# ADC.net
KiCad netlist of a schematic drawn in Altium Designer
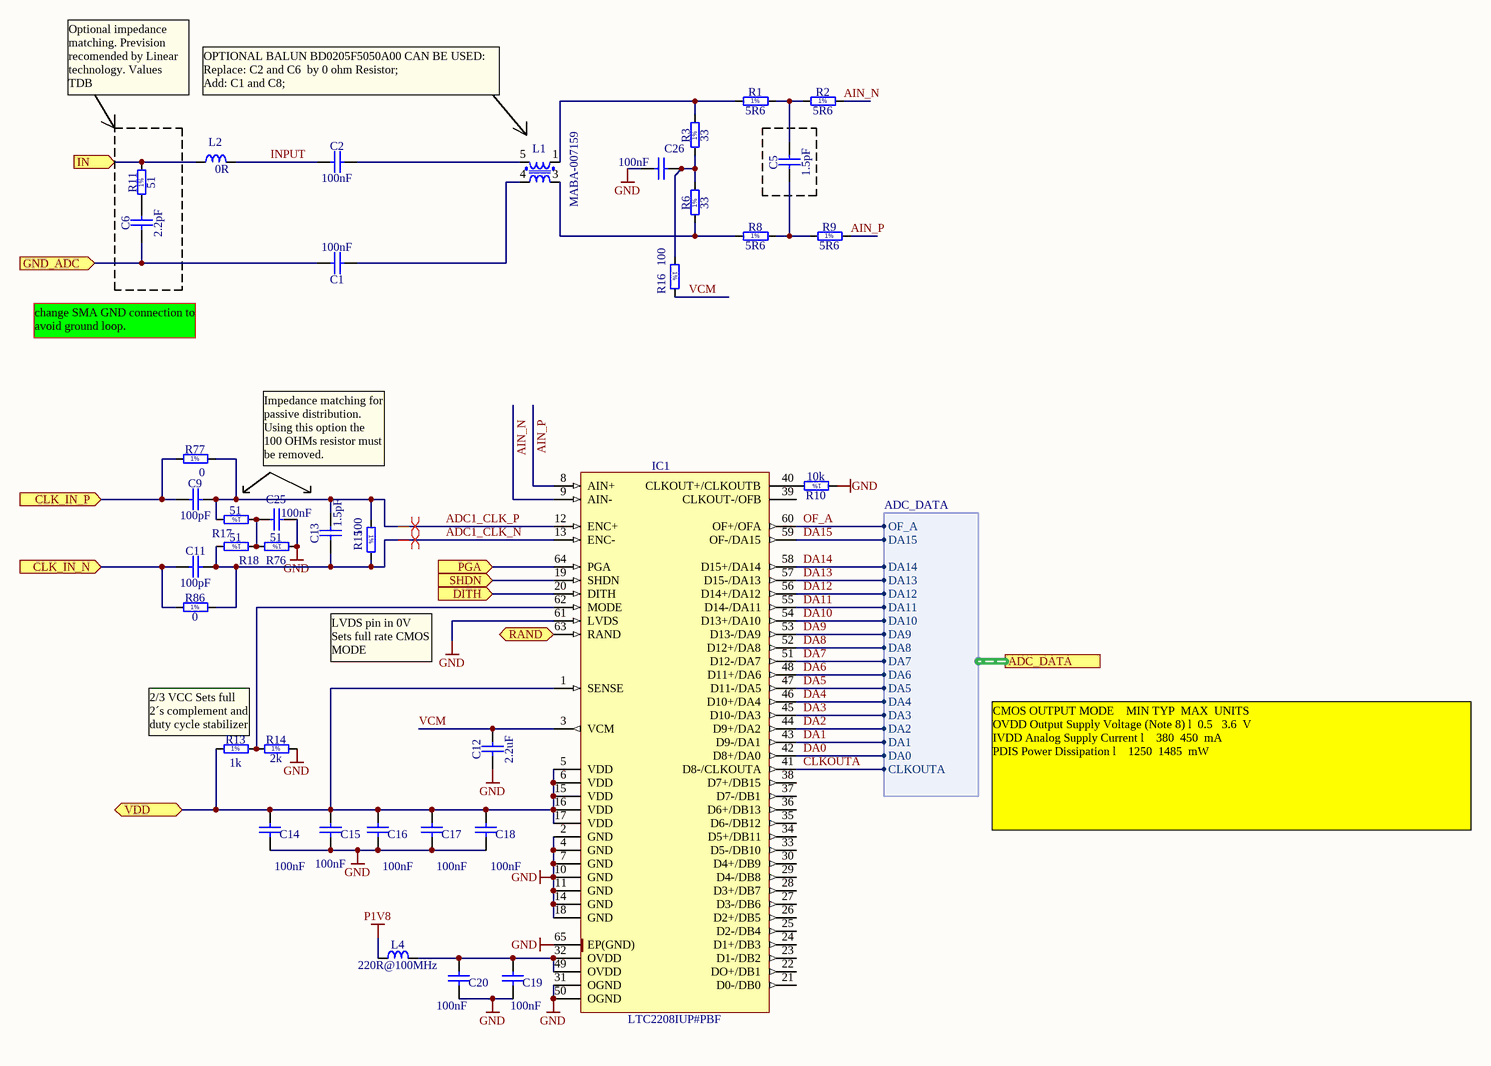
[diagram p0: ADC.SchDoc]

(export (version "E")
  (design (tool "Eeschema 10.0.6"))
  (components
    (comp (ref "C1")
      (value "100nF")
      (footprint "CAPC0603X33N")
      (description "Non-polarised capacitor")
      (fields
        (field (name "PART NUMBER") "CC0201_100NF_6.3V_10%_X5R")
        (field (name "VOLTAGE") "6.3V")
        (field (name "AUTHOR") "CERN DEM JLC")
      )
      (libsource (lib "Capacitors") (part "Capacitor - non polarized"))
    )
    (comp (ref "C2")
      (value "100nF")
      (footprint "CAPC0603X33N")
      (description "Non-polarised capacitor")
      (fields
        (field (name "PART NUMBER") "CC0201_100NF_6.3V_10%_X5R")
        (field (name "VOLTAGE") "6.3V")
        (field (name "AUTHOR") "CERN DEM JLC")
      )
      (libsource (lib "Capacitors") (part "Capacitor - non polarized"))
    )
    (comp (ref "C5")
      (value "1.5pF")
      (footprint "CAPC1005X55N")
      (description "Non-polarised capacitor")
      (fields
        (field (name "PART NUMBER") "CC0402_1.5PF_50V_0.25PF_NP0")
        (field (name "VOLTAGE") "50V")
        (field (name "AUTHOR") "CERN DEM JLC")
      )
      (libsource (lib "Capacitors") (part "Capacitor - non polarized"))
    )
    (comp (ref "C6")
      (value "2.2pF")
      (footprint "CAPC1005X55N")
      (description "Non-polarised capacitor")
      (fields
        (field (name "PART NUMBER") "CC0402_2.2PF_50V_0.25PF_NP0")
        (field (name "VOLTAGE") "50V")
        (field (name "AUTHOR") "CERN DEM JLC")
      )
      (libsource (lib "Capacitors") (part "Capacitor - non polarized"))
    )
    (comp (ref "C9")
      (value "100pF")
      (footprint "CAPC1005X55N")
      (description "Non-polarised capacitor")
      (fields
        (field (name "PART NUMBER") "CC0402_100PF_50V_5%_NP0")
        (field (name "VOLTAGE") "50V")
        (field (name "AUTHOR") "CERN DEM JLC")
      )
      (libsource (lib "Capacitors") (part "Capacitor - non polarized"))
    )
    (comp (ref "C11")
      (value "100pF")
      (footprint "CAPC1005X55N")
      (description "Non-polarised capacitor")
      (fields
        (field (name "PART NUMBER") "CC0402_100PF_50V_5%_NP0")
        (field (name "VOLTAGE") "50V")
        (field (name "AUTHOR") "CERN DEM JLC")
      )
      (libsource (lib "Capacitors") (part "Capacitor - non polarized"))
    )
    (comp (ref "C12")
      (value "2.2uF")
      (footprint "CAPC1608X87N")
      (description "Non-polarised capacitor")
      (fields
        (field (name "PART NUMBER") "CC0603_2.2UF_16V_10%_X5R")
        (field (name "VOLTAGE") "16V")
        (field (name "AUTHOR") "CERN DEM JLC")
      )
      (libsource (lib "Capacitors") (part "Capacitor - non polarized"))
    )
    (comp (ref "C13")
      (value "1.5pF")
      (footprint "CAPC1005X55N")
      (description "Non-polarised capacitor")
      (fields
        (field (name "PART NUMBER") "CC0402_1.5PF_50V_0.25PF_NP0")
        (field (name "VOLTAGE") "50V")
        (field (name "AUTHOR") "CERN DEM JLC")
      )
      (libsource (lib "Capacitors") (part "Capacitor - non polarized"))
    )
    (comp (ref "C14")
      (value "100nF")
      (footprint "CAPC0603X33N")
      (description "Non-polarised capacitor")
      (fields
        (field (name "PART NUMBER") "CC0201_100NF_6.3V_10%_X5R")
        (field (name "VOLTAGE") "6.3V")
        (field (name "AUTHOR") "CERN DEM JLC")
      )
      (libsource (lib "Capacitors") (part "Capacitor - non polarized"))
    )
    (comp (ref "C15")
      (value "100nF")
      (footprint "CAPC0603X33N")
      (description "Non-polarised capacitor")
      (fields
        (field (name "PART NUMBER") "CC0201_100NF_6.3V_10%_X5R")
        (field (name "VOLTAGE") "6.3V")
        (field (name "AUTHOR") "CERN DEM JLC")
      )
      (libsource (lib "Capacitors") (part "Capacitor - non polarized"))
    )
    (comp (ref "C16")
      (value "100nF")
      (footprint "CAPC0603X33N")
      (description "Non-polarised capacitor")
      (fields
        (field (name "PART NUMBER") "CC0201_100NF_6.3V_10%_X5R")
        (field (name "VOLTAGE") "6.3V")
        (field (name "AUTHOR") "CERN DEM JLC")
      )
      (libsource (lib "Capacitors") (part "Capacitor - non polarized"))
    )
    (comp (ref "C17")
      (value "100nF")
      (footprint "CAPC0603X33N")
      (description "Non-polarised capacitor")
      (fields
        (field (name "PART NUMBER") "CC0201_100NF_6.3V_10%_X5R")
        (field (name "VOLTAGE") "6.3V")
        (field (name "AUTHOR") "CERN DEM JLC")
      )
      (libsource (lib "Capacitors") (part "Capacitor - non polarized"))
    )
    (comp (ref "C18")
      (value "100nF")
      (footprint "CAPC0603X33N")
      (description "Non-polarised capacitor")
      (fields
        (field (name "PART NUMBER") "CC0201_100NF_6.3V_10%_X5R")
        (field (name "VOLTAGE") "6.3V")
        (field (name "AUTHOR") "CERN DEM JLC")
      )
      (libsource (lib "Capacitors") (part "Capacitor - non polarized"))
    )
    (comp (ref "C19")
      (value "100nF")
      (footprint "CAPC0603X33N")
      (description "Non-polarised capacitor")
      (fields
        (field (name "PART NUMBER") "CC0201_100NF_6.3V_10%_X5R")
        (field (name "VOLTAGE") "6.3V")
        (field (name "AUTHOR") "CERN DEM JLC")
      )
      (libsource (lib "Capacitors") (part "Capacitor - non polarized"))
    )
    (comp (ref "C20")
      (value "100nF")
      (footprint "CAPC0603X33N")
      (description "Non-polarised capacitor")
      (fields
        (field (name "PART NUMBER") "CC0201_100NF_6.3V_10%_X5R")
        (field (name "VOLTAGE") "6.3V")
        (field (name "AUTHOR") "CERN DEM JLC")
      )
      (libsource (lib "Capacitors") (part "Capacitor - non polarized"))
    )
    (comp (ref "C25")
      (value "100nF")
      (footprint "CAPC0603X33N")
      (description "Non-polarised capacitor")
      (fields
        (field (name "PART NUMBER") "CC0201_100NF_6.3V_10%_X5R")
        (field (name "VOLTAGE") "6.3V")
        (field (name "AUTHOR") "CERN DEM JLC")
      )
      (libsource (lib "Capacitors") (part "Capacitor - non polarized"))
    )
    (comp (ref "C26")
      (value "100nF")
      (footprint "CAPC0603X33N")
      (description "Non-polarised capacitor")
      (fields
        (field (name "PART NUMBER") "CC0201_100NF_6.3V_10%_X5R")
        (field (name "VOLTAGE") "6.3V")
        (field (name "AUTHOR") "CERN DEM JLC")
      )
      (libsource (lib "Capacitors") (part "Capacitor - non polarized"))
    )
    (comp (ref "IC1")
      (value "LTC2208IUP#PBF")
      (footprint "QFN50P900X900X80-65N-S725")
      (description "16-Bit, 130Msps ADC")
      (fields
        (field (name "PART NUMBER") "LTC2LTC2208IUP#PBF")
        (field (name "MANUFACTURER") "LINEAR TECHNOLOGY")
        (field (name "AUTHOR") "CERN DEM JLC")
      )
      (libsource (lib "ICs And Semiconductors") (part "LTC2208"))
    )
    (comp (ref "L1")
      (value "MABA-007159")
      (footprint "XFMR_MA-COM_SM-22 (H260)")
      (description "MA-COM E-Serie RF 1:1 Transmission Line Ttransformer 4.5-3000MHz")
      (libsource (lib "fmclib") (part "XFMR_MA-COM_MABA-007159-000000_modified"))
    )
    (comp (ref "L2")
      (value "0R")
      (footprint "INDC1005X55N")
      (description "Inductor")
      (fields
        (field (name "PART NUMBER") "IND0402_MURATA_BLM15HB221SN1")
        (field (name "POWER") "250mA")
        (field (name "AUTHOR") "CERN DEM JLC")
      )
      (libsource (lib "Inductors & Transformers") (part "Inductor"))
    )
    (comp (ref "L4")
      (value "220R@100MHz")
      (footprint "INDC2012X105N")
      (description "Inductor")
      (fields
        (field (name "PART NUMBER") "IND0805_MURATA_BLM21PG221SN1D")
        (field (name "POWER") "2A")
        (field (name "AUTHOR") "CERN DEM JLC")
      )
      (libsource (lib "Inductors & Transformers") (part "Inductor"))
    )
    (comp (ref "R1")
      (value "5R6")
      (footprint "RESC1005X40N")
      (description "Resistor - 1%")
      (fields
        (field (name "PART NUMBER") "R0402_5R6_1%_0.0625W_200PPM")
        (field (name "POWER") "0.0625W")
        (field (name "AUTHOR") "CERN DEM JLC")
      )
      (libsource (lib "Resistors") (part "Resistor - 1%"))
    )
    (comp (ref "R2")
      (value "5R6")
      (footprint "RESC1005X40N")
      (description "Resistor - 1%")
      (fields
        (field (name "PART NUMBER") "R0402_5R6_1%_0.0625W_200PPM")
        (field (name "POWER") "0.0625W")
        (field (name "AUTHOR") "CERN DEM JLC")
      )
      (libsource (lib "Resistors") (part "Resistor - 1%"))
    )
    (comp (ref "R3")
      (value "33")
      (footprint "RESC1005X40N")
      (description "Resistor - 1%")
      (fields
        (field (name "PART NUMBER") "R0402_33R_1%_0.0625W_100PPM")
        (field (name "POWER") "0.0625W")
        (field (name "AUTHOR") "CERN DEM JLC")
      )
      (libsource (lib "Resistors") (part "Resistor - 1%"))
    )
    (comp (ref "R6")
      (value "33")
      (footprint "RESC1005X40N")
      (description "Resistor - 1%")
      (fields
        (field (name "PART NUMBER") "R0402_33R_1%_0.0625W_100PPM")
        (field (name "POWER") "0.0625W")
        (field (name "AUTHOR") "CERN DEM JLC")
      )
      (libsource (lib "Resistors") (part "Resistor - 1%"))
    )
    (comp (ref "R8")
      (value "5R6")
      (footprint "RESC1005X40N")
      (description "Resistor - 1%")
      (fields
        (field (name "PART NUMBER") "R0402_5R6_1%_0.0625W_200PPM")
        (field (name "POWER") "0.0625W")
        (field (name "AUTHOR") "CERN DEM JLC")
      )
      (libsource (lib "Resistors") (part "Resistor - 1%"))
    )
    (comp (ref "R9")
      (value "5R6")
      (footprint "RESC1005X40N")
      (description "Resistor - 1%")
      (fields
        (field (name "PART NUMBER") "R0402_5R6_1%_0.0625W_200PPM")
        (field (name "POWER") "0.0625W")
        (field (name "AUTHOR") "CERN DEM JLC")
      )
      (libsource (lib "Resistors") (part "Resistor - 1%"))
    )
    (comp (ref "R10")
      (value "10k")
      (footprint "RESC1005X40N")
      (description "Resistor - 1%")
      (fields
        (field (name "PART NUMBER") "R0402_10K_1%_0.0625W_100PPM")
        (field (name "POWER") "0.0625W")
        (field (name "AUTHOR") "CERN DEM JLC")
      )
      (libsource (lib "Resistors") (part "Resistor - 1%"))
    )
    (comp (ref "R11")
      (value "51")
      (footprint "RESC1005X40N")
      (description "Resistor - 1%")
      (fields
        (field (name "PART NUMBER") "R0402_51R_1%_0.0625W_100PPM")
        (field (name "POWER") "0.0625W")
        (field (name "AUTHOR") "CERN DEM JLC")
      )
      (libsource (lib "Resistors") (part "Resistor - 1%"))
    )
    (comp (ref "R13")
      (value "1k")
      (footprint "RESC1005X40N")
      (description "Resistor - 1%")
      (fields
        (field (name "PART NUMBER") "R0402_1K_1%_0.0625W_100PPM")
        (field (name "POWER") "0.0625W")
        (field (name "AUTHOR") "CERN DEM JLC")
      )
      (libsource (lib "Resistors") (part "Resistor - 1%"))
    )
    (comp (ref "R14")
      (value "2k")
      (footprint "RESC1005X40N")
      (description "Resistor - 1%")
      (fields
        (field (name "PART NUMBER") "R0402_2K_1%_0.0625W_100PPM")
        (field (name "POWER") "0.0625W")
        (field (name "AUTHOR") "CERN DEM JLC")
      )
      (libsource (lib "Resistors") (part "Resistor - 1%"))
    )
    (comp (ref "R15")
      (value "100")
      (footprint "RESC1005X40N")
      (description "Resistor - 1%")
      (fields
        (field (name "PART NUMBER") "R0402_100R_1%_0.0625W_100PPM")
        (field (name "POWER") "0.0625W")
        (field (name "AUTHOR") "CERN DEM JLC")
      )
      (libsource (lib "Resistors") (part "Resistor - 1%"))
    )
    (comp (ref "R16")
      (value "100")
      (footprint "RESC1005X40N")
      (description "Resistor - 1%")
      (fields
        (field (name "PART NUMBER") "R0402_100R_1%_0.0625W_100PPM")
        (field (name "POWER") "0.0625W")
        (field (name "AUTHOR") "CERN DEM JLC")
      )
      (libsource (lib "Resistors") (part "Resistor - 1%"))
    )
    (comp (ref "R17")
      (value "51")
      (footprint "RESC1005X40N")
      (description "Resistor - 1%")
      (fields
        (field (name "PART NUMBER") "R0402_51R_1%_0.0625W_100PPM")
        (field (name "POWER") "0.0625W")
        (field (name "AUTHOR") "CERN DEM JLC")
      )
      (libsource (lib "Resistors") (part "Resistor - 1%"))
    )
    (comp (ref "R18")
      (value "51")
      (footprint "RESC1005X40N")
      (description "Resistor - 1%")
      (fields
        (field (name "PART NUMBER") "R0402_51R_1%_0.0625W_100PPM")
        (field (name "POWER") "0.0625W")
        (field (name "AUTHOR") "CERN DEM JLC")
      )
      (libsource (lib "Resistors") (part "Resistor - 1%"))
    )
    (comp (ref "R76")
      (value "51")
      (footprint "RESC1005X40N")
      (description "Resistor - 1%")
      (fields
        (field (name "PART NUMBER") "R0402_51R_1%_0.0625W_100PPM")
        (field (name "POWER") "0.0625W")
        (field (name "AUTHOR") "CERN DEM JLC")
      )
      (libsource (lib "Resistors") (part "Resistor - 1%"))
    )
    (comp (ref "R77")
      (value "0")
      (footprint "RESC1005X40N")
      (description "Resistor - 1%")
      (fields
        (field (name "PART NUMBER") "R0402_0R_JUMPER")
        (field (name "MANUFACTURER") "GENERIC")
        (field (name "AUTHOR") "CERN DEM JLC")
      )
      (libsource (lib "Resistors") (part "Resistor - 1%"))
    )
    (comp (ref "R86")
      (value "0")
      (footprint "RESC1005X40N")
      (description "Resistor - 1%")
      (fields
        (field (name "PART NUMBER") "R0402_0R_JUMPER")
        (field (name "MANUFACTURER") "GENERIC")
        (field (name "AUTHOR") "CERN DEM JLC")
      )
      (libsource (lib "Resistors") (part "Resistor - 1%"))
    )
  )
  (nets
    (net (code "2") (name "/ADC1_CLK_N") (class "Default")
      (node (ref "C11") (pin "2") (pinfunction "2_2") (pintype "passive"))
      (node (ref "C13") (pin "1") (pinfunction "1_1") (pintype "passive"))
      (node (ref "IC1") (pin "13") (pinfunction "ENC-_13") (pintype "input"))
      (node (ref "R15") (pin "2") (pinfunction "2_2") (pintype "passive"))
      (node (ref "R18") (pin "2") (pinfunction "2_2") (pintype "passive"))
      (node (ref "R86") (pin "2") (pinfunction "2_2") (pintype "passive"))
    )
    (net (code "3") (name "/ADC1_CLK_P") (class "Default")
      (node (ref "C13") (pin "2") (pinfunction "2_2") (pintype "passive"))
      (node (ref "C9") (pin "2") (pinfunction "2_2") (pintype "passive"))
      (node (ref "IC1") (pin "12") (pinfunction "ENC+_12") (pintype "input"))
      (node (ref "R15") (pin "1") (pinfunction "1_1") (pintype "passive"))
      (node (ref "R17") (pin "2") (pinfunction "2_2") (pintype "passive"))
      (node (ref "R77") (pin "2") (pinfunction "2_2") (pintype "passive"))
    )
    (net (code "4") (name "/AIN_N") (class "Default")
      (node (ref "IC1") (pin "9") (pinfunction "AIN-_9") (pintype "input"))
      (node (ref "R2") (pin "2") (pinfunction "2_2") (pintype "passive"))
    )
    (net (code "5") (name "/AIN_P") (class "Default")
      (node (ref "IC1") (pin "8") (pinfunction "AIN+_8") (pintype "input"))
      (node (ref "R9") (pin "2") (pinfunction "2_2") (pintype "passive"))
    )
    (net (code "6") (name "/CLKOUTA") (class "Default")
      (node (ref "IC1") (pin "41") (pinfunction "D8-/CLKOUTA_41") (pintype "output"))
    )
    (net (code "7") (name "/CLK_IN_N") (class "Default")
      (node (ref "C11") (pin "1") (pinfunction "1_1") (pintype "passive"))
      (node (ref "R86") (pin "1") (pinfunction "1_1") (pintype "passive"))
    )
    (net (code "8") (name "/CLK_IN_P") (class "Default")
      (node (ref "C9") (pin "1") (pinfunction "1_1") (pintype "passive"))
      (node (ref "R77") (pin "1") (pinfunction "1_1") (pintype "passive"))
    )
    (net (code "9") (name "/DA0") (class "Default")
      (node (ref "IC1") (pin "42") (pinfunction "D8+/DA0_42") (pintype "output"))
    )
    (net (code "10") (name "/DA1") (class "Default")
      (node (ref "IC1") (pin "43") (pinfunction "D9-/DA1_43") (pintype "output"))
    )
    (net (code "11") (name "/DA2") (class "Default")
      (node (ref "IC1") (pin "44") (pinfunction "D9+/DA2_44") (pintype "output"))
    )
    (net (code "12") (name "/DA3") (class "Default")
      (node (ref "IC1") (pin "45") (pinfunction "D10-/DA3_45") (pintype "output"))
    )
    (net (code "13") (name "/DA4") (class "Default")
      (node (ref "IC1") (pin "46") (pinfunction "D10+/DA4_46") (pintype "output"))
    )
    (net (code "14") (name "/DA5") (class "Default")
      (node (ref "IC1") (pin "47") (pinfunction "D11-/DA5_47") (pintype "output"))
    )
    (net (code "15") (name "/DA6") (class "Default")
      (node (ref "IC1") (pin "48") (pinfunction "D11+/DA6_48") (pintype "output"))
    )
    (net (code "16") (name "/DA7") (class "Default")
      (node (ref "IC1") (pin "51") (pinfunction "D12-/DA7_51") (pintype "output"))
    )
    (net (code "17") (name "/DA8") (class "Default")
      (node (ref "IC1") (pin "52") (pinfunction "D12+/DA8_52") (pintype "output"))
    )
    (net (code "18") (name "/DA9") (class "Default")
      (node (ref "IC1") (pin "53") (pinfunction "D13-/DA9_53") (pintype "output"))
    )
    (net (code "19") (name "/DA10") (class "Default")
      (node (ref "IC1") (pin "54") (pinfunction "D13+/DA10_54") (pintype "output"))
    )
    (net (code "20") (name "/DA11") (class "Default")
      (node (ref "IC1") (pin "55") (pinfunction "D14-/DA11_55") (pintype "output"))
    )
    (net (code "21") (name "/DA12") (class "Default")
      (node (ref "IC1") (pin "56") (pinfunction "D14+/DA12_56") (pintype "output"))
    )
    (net (code "22") (name "/DA13") (class "Default")
      (node (ref "IC1") (pin "57") (pinfunction "D15-/DA13_57") (pintype "output"))
    )
    (net (code "23") (name "/DA14") (class "Default")
      (node (ref "IC1") (pin "58") (pinfunction "D15+/DA14_58") (pintype "output"))
    )
    (net (code "24") (name "/DA15") (class "Default")
      (node (ref "IC1") (pin "59") (pinfunction "OF-/DA15_59") (pintype "output"))
    )
    (net (code "25") (name "/DITH") (class "Default")
      (node (ref "IC1") (pin "20") (pinfunction "DITH_20") (pintype "input"))
    )
    (net (code "26") (name "/GND_ADC") (class "Default")
      (node (ref "C1") (pin "2") (pinfunction "2_2") (pintype "passive"))
      (node (ref "C6") (pin "1") (pinfunction "1_1") (pintype "passive"))
    )
    (net (code "27") (name "/IN") (class "Default")
      (node (ref "L2") (pin "1") (pinfunction "1_1") (pintype "passive"))
      (node (ref "R11") (pin "2") (pinfunction "2_2") (pintype "passive"))
    )
    (net (code "28") (name "/INPUT") (class "Default")
      (node (ref "C2") (pin "1") (pinfunction "1_1") (pintype "passive"))
      (node (ref "L2") (pin "2") (pinfunction "2_2") (pintype "passive"))
    )
    (net (code "29") (name "/OF_A") (class "Default")
      (node (ref "IC1") (pin "60") (pinfunction "OF+/OFA_60") (pintype "output"))
    )
    (net (code "30") (name "/PGA") (class "Default")
      (node (ref "IC1") (pin "64") (pinfunction "PGA_64") (pintype "input"))
    )
    (net (code "31") (name "/RAND") (class "Default")
      (node (ref "IC1") (pin "63") (pinfunction "RAND_63") (pintype "input"))
    )
    (net (code "32") (name "/SHDN") (class "Default")
      (node (ref "IC1") (pin "19") (pinfunction "SHDN_19") (pintype "input"))
    )
    (net (code "33") (name "/VCM") (class "Default")
      (node (ref "C12") (pin "2") (pinfunction "2_2") (pintype "passive"))
      (node (ref "IC1") (pin "3") (pinfunction "VCM_3") (pintype "output"))
      (node (ref "R16") (pin "2") (pinfunction "2_2") (pintype "passive"))
    )
    (net (code "34") (name "/VDD") (class "Default")
      (node (ref "C14") (pin "2") (pinfunction "2_2") (pintype "passive"))
      (node (ref "C15") (pin "2") (pinfunction "2_2") (pintype "passive"))
      (node (ref "C16") (pin "2") (pinfunction "2_2") (pintype "passive"))
      (node (ref "C17") (pin "2") (pinfunction "2_2") (pintype "passive"))
      (node (ref "C18") (pin "2") (pinfunction "2_2") (pintype "passive"))
      (node (ref "IC1") (pin "1") (pinfunction "SENSE_1") (pintype "input"))
      (node (ref "IC1") (pin "15") (pinfunction "VDD_15") (pintype "power_in"))
      (node (ref "IC1") (pin "16") (pinfunction "VDD_16") (pintype "power_in"))
      (node (ref "IC1") (pin "17") (pinfunction "VDD_17") (pintype "power_in"))
      (node (ref "IC1") (pin "5") (pinfunction "VDD_5") (pintype "power_in"))
      (node (ref "IC1") (pin "6") (pinfunction "VDD_6") (pintype "power_in"))
      (node (ref "R13") (pin "1") (pinfunction "1_1") (pintype "passive"))
    )
    (net (code "36") (name "GND") (class "Default")
      (node (ref "C12") (pin "1") (pinfunction "1_1") (pintype "passive"))
      (node (ref "C14") (pin "1") (pinfunction "1_1") (pintype "passive"))
      (node (ref "C15") (pin "1") (pinfunction "1_1") (pintype "passive"))
      (node (ref "C16") (pin "1") (pinfunction "1_1") (pintype "passive"))
      (node (ref "C17") (pin "1") (pinfunction "1_1") (pintype "passive"))
      (node (ref "C18") (pin "1") (pinfunction "1_1") (pintype "passive"))
      (node (ref "C19") (pin "1") (pinfunction "1_1") (pintype "passive"))
      (node (ref "C20") (pin "1") (pinfunction "1_1") (pintype "passive"))
      (node (ref "C25") (pin "1") (pinfunction "1_1") (pintype "passive"))
      (node (ref "C26") (pin "2") (pinfunction "2_2") (pintype "passive"))
      (node (ref "IC1") (pin "10") (pinfunction "GND_10") (pintype "power_in"))
      (node (ref "IC1") (pin "11") (pinfunction "GND_11") (pintype "power_in"))
      (node (ref "IC1") (pin "14") (pinfunction "GND_14") (pintype "power_in"))
      (node (ref "IC1") (pin "18") (pinfunction "GND_18") (pintype "power_in"))
      (node (ref "IC1") (pin "2") (pinfunction "GND_2") (pintype "power_in"))
      (node (ref "IC1") (pin "31") (pinfunction "OGND_31") (pintype "power_in"))
      (node (ref "IC1") (pin "4") (pinfunction "GND_4") (pintype "power_in"))
      (node (ref "IC1") (pin "50") (pinfunction "OGND_50") (pintype "power_in"))
      (node (ref "IC1") (pin "61") (pinfunction "LVDS_61") (pintype "input"))
      (node (ref "IC1") (pin "65") (pinfunction "EP(GND)_65") (pintype "power_in"))
      (node (ref "IC1") (pin "7") (pinfunction "GND_7") (pintype "power_in"))
      (node (ref "R10") (pin "1") (pinfunction "1_1") (pintype "passive"))
      (node (ref "R14") (pin "2") (pinfunction "2_2") (pintype "passive"))
      (node (ref "R76") (pin "1") (pinfunction "1_1") (pintype "passive"))
    )
    (net (code "37") (name "Net-(C1-Pad1)") (class "Default")
      (node (ref "C1") (pin "1") (pinfunction "1_1") (pintype "passive"))
      (node (ref "L1") (pin "4") (pinfunction "4_4") (pintype "passive"))
    )
    (net (code "38") (name "Net-(C2-Pad2)") (class "Default")
      (node (ref "C2") (pin "2") (pinfunction "2_2") (pintype "passive"))
      (node (ref "L1") (pin "5") (pinfunction "5_5") (pintype "passive"))
    )
    (net (code "39") (name "Net-(C5-Pad1)") (class "Default")
      (node (ref "C5") (pin "1") (pinfunction "1_1") (pintype "passive"))
      (node (ref "R8") (pin "2") (pinfunction "2_2") (pintype "passive"))
      (node (ref "R9") (pin "1") (pinfunction "1_1") (pintype "passive"))
    )
    (net (code "40") (name "Net-(C5-Pad2)") (class "Default")
      (node (ref "C5") (pin "2") (pinfunction "2_2") (pintype "passive"))
      (node (ref "R1") (pin "2") (pinfunction "2_2") (pintype "passive"))
      (node (ref "R2") (pin "1") (pinfunction "1_1") (pintype "passive"))
    )
    (net (code "41") (name "Net-(C6-Pad2)") (class "Default")
      (node (ref "C6") (pin "2") (pinfunction "2_2") (pintype "passive"))
      (node (ref "R11") (pin "1") (pinfunction "1_1") (pintype "passive"))
    )
    (net (code "42") (name "Net-(C19-Pad2)") (class "Default")
      (node (ref "C19") (pin "2") (pinfunction "2_2") (pintype "passive"))
      (node (ref "C20") (pin "2") (pinfunction "2_2") (pintype "passive"))
      (node (ref "IC1") (pin "32") (pinfunction "OVDD_32") (pintype "power_in"))
      (node (ref "IC1") (pin "49") (pinfunction "OVDD_49") (pintype "power_in"))
      (node (ref "L4") (pin "2") (pinfunction "2_2") (pintype "passive"))
    )
    (net (code "43") (name "Net-(C25-Pad2)") (class "Default")
      (node (ref "C25") (pin "2") (pinfunction "2_2") (pintype "passive"))
      (node (ref "R17") (pin "1") (pinfunction "1_1") (pintype "passive"))
      (node (ref "R18") (pin "1") (pinfunction "1_1") (pintype "passive"))
      (node (ref "R76") (pin "2") (pinfunction "2_2") (pintype "passive"))
    )
    (net (code "44") (name "Net-(C26-Pad1)") (class "Default")
      (node (ref "C26") (pin "1") (pinfunction "1_1") (pintype "passive"))
      (node (ref "R16") (pin "1") (pinfunction "1_1") (pintype "passive"))
      (node (ref "R3") (pin "1") (pinfunction "1_1") (pintype "passive"))
      (node (ref "R6") (pin "2") (pinfunction "2_2") (pintype "passive"))
    )
    (net (code "45") (name "Net-(IC1-CLKOUT+{slash}CLKOUTB)") (class "Default")
      (node (ref "IC1") (pin "40") (pinfunction "CLKOUT+/CLKOUTB_40") (pintype "power_in"))
      (node (ref "R10") (pin "2") (pinfunction "2_2") (pintype "passive"))
    )
    (net (code "46") (name "Net-(IC1-MODE)") (class "Default")
      (node (ref "IC1") (pin "62") (pinfunction "MODE_62") (pintype "input"))
      (node (ref "R13") (pin "2") (pinfunction "2_2") (pintype "passive"))
      (node (ref "R14") (pin "1") (pinfunction "1_1") (pintype "passive"))
    )
    (net (code "47") (name "Net-(L1-Pad1)") (class "Default")
      (node (ref "L1") (pin "1") (pinfunction "1_1") (pintype "passive"))
      (node (ref "R1") (pin "1") (pinfunction "1_1") (pintype "passive"))
      (node (ref "R3") (pin "2") (pinfunction "2_2") (pintype "passive"))
    )
    (net (code "48") (name "Net-(L1-Pad3)") (class "Default")
      (node (ref "L1") (pin "3") (pinfunction "3_3") (pintype "passive"))
      (node (ref "R6") (pin "1") (pinfunction "1_1") (pintype "passive"))
      (node (ref "R8") (pin "1") (pinfunction "1_1") (pintype "passive"))
    )
    (net (code "49") (name "P1V8") (class "Default")
      (node (ref "L4") (pin "1") (pinfunction "1_1") (pintype "passive"))
    )
    (net (code "50") (name "unconnected-(IC1-CLKOUT-{slash}OFB-Pad39)") (class "Default")
      (node (ref "IC1") (pin "39") (pinfunction "CLKOUT-/OFB_39") (pintype "power_in"))
    )
    (net (code "51") (name "unconnected-(IC1-D0-{slash}DB0-Pad21)") (class "Default")
      (node (ref "IC1") (pin "21") (pinfunction "D0-/DB0_21") (pintype "output"))
    )
    (net (code "52") (name "unconnected-(IC1-D1+{slash}DB3-Pad24)") (class "Default")
      (node (ref "IC1") (pin "24") (pinfunction "D1+/DB3_24") (pintype "output"))
    )
    (net (code "53") (name "unconnected-(IC1-D1-{slash}DB2-Pad23)") (class "Default")
      (node (ref "IC1") (pin "23") (pinfunction "D1-/DB2_23") (pintype "output"))
    )
    (net (code "54") (name "unconnected-(IC1-D2+{slash}DB5-Pad26)") (class "Default")
      (node (ref "IC1") (pin "26") (pinfunction "D2+/DB5_26") (pintype "output"))
    )
    (net (code "55") (name "unconnected-(IC1-D2-{slash}DB4-Pad25)") (class "Default")
      (node (ref "IC1") (pin "25") (pinfunction "D2-/DB4_25") (pintype "output"))
    )
    (net (code "56") (name "unconnected-(IC1-D3+{slash}DB7-Pad28)") (class "Default")
      (node (ref "IC1") (pin "28") (pinfunction "D3+/DB7_28") (pintype "output"))
    )
    (net (code "57") (name "unconnected-(IC1-D3-{slash}DB6-Pad27)") (class "Default")
      (node (ref "IC1") (pin "27") (pinfunction "D3-/DB6_27") (pintype "output"))
    )
    (net (code "58") (name "unconnected-(IC1-D4+{slash}DB9-Pad30)") (class "Default")
      (node (ref "IC1") (pin "30") (pinfunction "D4+/DB9_30") (pintype "output"))
    )
    (net (code "59") (name "unconnected-(IC1-D4-{slash}DB8-Pad29)") (class "Default")
      (node (ref "IC1") (pin "29") (pinfunction "D4-/DB8_29") (pintype "output"))
    )
    (net (code "60") (name "unconnected-(IC1-D5+{slash}DB11-Pad34)") (class "Default")
      (node (ref "IC1") (pin "34") (pinfunction "D5+/DB11_34") (pintype "output"))
    )
    (net (code "61") (name "unconnected-(IC1-D5-{slash}DB10-Pad33)") (class "Default")
      (node (ref "IC1") (pin "33") (pinfunction "D5-/DB10_33") (pintype "output"))
    )
    (net (code "62") (name "unconnected-(IC1-D6+{slash}DB13-Pad36)") (class "Default")
      (node (ref "IC1") (pin "36") (pinfunction "D6+/DB13_36") (pintype "output"))
    )
    (net (code "63") (name "unconnected-(IC1-D6-{slash}DB12-Pad35)") (class "Default")
      (node (ref "IC1") (pin "35") (pinfunction "D6-/DB12_35") (pintype "output"))
    )
    (net (code "64") (name "unconnected-(IC1-D7+{slash}DB15-Pad38)") (class "Default")
      (node (ref "IC1") (pin "38") (pinfunction "D7+/DB15_38") (pintype "output"))
    )
    (net (code "65") (name "unconnected-(IC1-D7-{slash}DB1-Pad37)") (class "Default")
      (node (ref "IC1") (pin "37") (pinfunction "D7-/DB1_37") (pintype "output"))
    )
    (net (code "66") (name "unconnected-(IC1-DO+{slash}DB1-Pad22)") (class "Default")
      (node (ref "IC1") (pin "22") (pinfunction "DO+/DB1_22") (pintype "output"))
    )
  )
)
